# OutputConnectors.net
KiCad netlist of a schematic drawn in Altium Designer
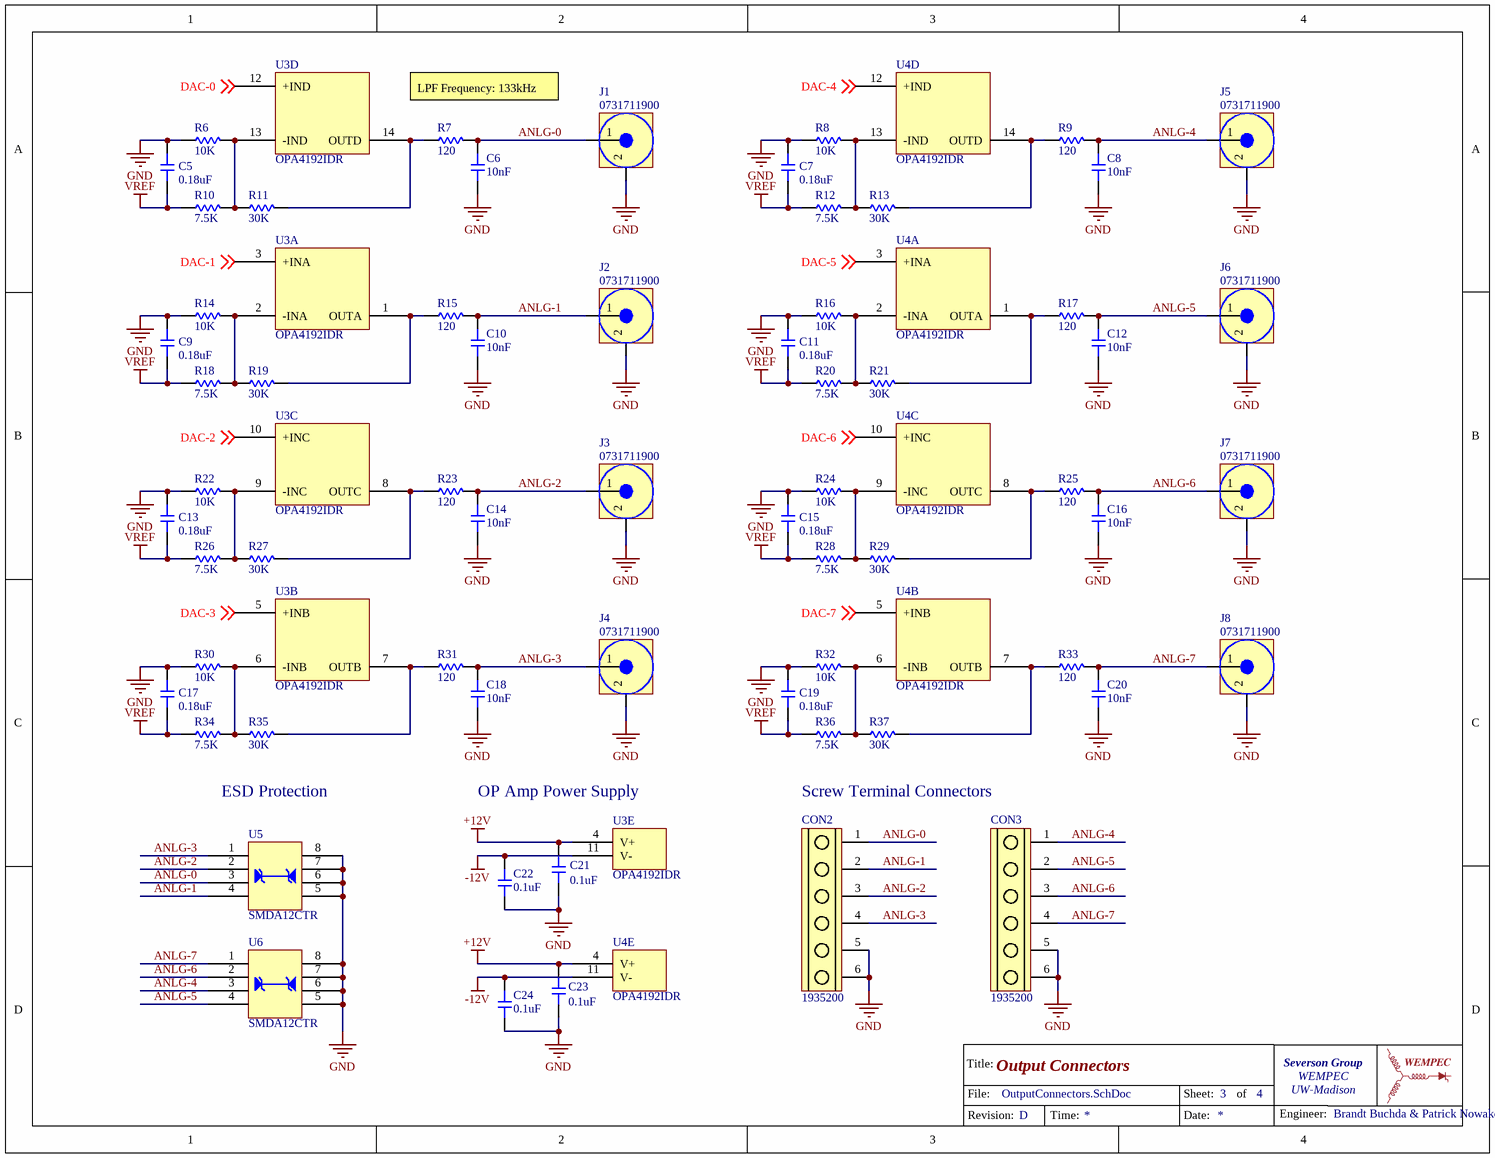
[diagram p0: OutputConnectors.SchDoc]

(export (version "E")
  (design (tool "Eeschema 10.0.6"))
  (components
    (comp (ref "C5")
      (value "0.18uF")
      (footprint "0603-CAP")
      (description "0.18µF ±10% 16V Ceramic Capacitor X7R 0603 (1608 Metric)")
      (fields (field (name "Comment") "CC0603KRX7R7BB184"))
      (libsource (lib "DAC") (part "Capacitor 0.18uF"))
    )
    (comp (ref "C6")
      (value "10nF")
      (footprint "0603-CAP")
      (description "10000pF ±10% 50V Ceramic Capacitor X7R 0603 (1608 Metric)")
      (fields (field (name "Comment") "CC0603KRX7R9BB103"))
      (libsource (lib "DAC") (part "Capacitor 10nF"))
    )
    (comp (ref "C7")
      (value "0.18uF")
      (footprint "0603-CAP")
      (description "0.18µF ±10% 16V Ceramic Capacitor X7R 0603 (1608 Metric)")
      (fields (field (name "Comment") "CC0603KRX7R7BB184"))
      (libsource (lib "DAC") (part "Capacitor 0.18uF"))
    )
    (comp (ref "C8")
      (value "10nF")
      (footprint "0603-CAP")
      (description "10000pF ±10% 50V Ceramic Capacitor X7R 0603 (1608 Metric)")
      (fields (field (name "Comment") "CC0603KRX7R9BB103"))
      (libsource (lib "DAC") (part "Capacitor 10nF"))
    )
    (comp (ref "C9")
      (value "0.18uF")
      (footprint "0603-CAP")
      (description "0.18µF ±10% 16V Ceramic Capacitor X7R 0603 (1608 Metric)")
      (fields (field (name "Comment") "CC0603KRX7R7BB184"))
      (libsource (lib "DAC") (part "Capacitor 0.18uF"))
    )
    (comp (ref "C10")
      (value "10nF")
      (footprint "0603-CAP")
      (description "10000pF ±10% 50V Ceramic Capacitor X7R 0603 (1608 Metric)")
      (fields (field (name "Comment") "CC0603KRX7R9BB103"))
      (libsource (lib "DAC") (part "Capacitor 10nF"))
    )
    (comp (ref "C11")
      (value "0.18uF")
      (footprint "0603-CAP")
      (description "0.18µF ±10% 16V Ceramic Capacitor X7R 0603 (1608 Metric)")
      (fields (field (name "Comment") "CC0603KRX7R7BB184"))
      (libsource (lib "DAC") (part "Capacitor 0.18uF"))
    )
    (comp (ref "C12")
      (value "10nF")
      (footprint "0603-CAP")
      (description "10000pF ±10% 50V Ceramic Capacitor X7R 0603 (1608 Metric)")
      (fields (field (name "Comment") "CC0603KRX7R9BB103"))
      (libsource (lib "DAC") (part "Capacitor 10nF"))
    )
    (comp (ref "C13")
      (value "0.18uF")
      (footprint "0603-CAP")
      (description "0.18µF ±10% 16V Ceramic Capacitor X7R 0603 (1608 Metric)")
      (fields (field (name "Comment") "CC0603KRX7R7BB184"))
      (libsource (lib "DAC") (part "Capacitor 0.18uF"))
    )
    (comp (ref "C14")
      (value "10nF")
      (footprint "0603-CAP")
      (description "10000pF ±10% 50V Ceramic Capacitor X7R 0603 (1608 Metric)")
      (fields (field (name "Comment") "CC0603KRX7R9BB103"))
      (libsource (lib "DAC") (part "Capacitor 10nF"))
    )
    (comp (ref "C15")
      (value "0.18uF")
      (footprint "0603-CAP")
      (description "0.18µF ±10% 16V Ceramic Capacitor X7R 0603 (1608 Metric)")
      (fields (field (name "Comment") "CC0603KRX7R7BB184"))
      (libsource (lib "DAC") (part "Capacitor 0.18uF"))
    )
    (comp (ref "C16")
      (value "10nF")
      (footprint "0603-CAP")
      (description "10000pF ±10% 50V Ceramic Capacitor X7R 0603 (1608 Metric)")
      (fields (field (name "Comment") "CC0603KRX7R9BB103"))
      (libsource (lib "DAC") (part "Capacitor 10nF"))
    )
    (comp (ref "C17")
      (value "0.18uF")
      (footprint "0603-CAP")
      (description "0.18µF ±10% 16V Ceramic Capacitor X7R 0603 (1608 Metric)")
      (fields (field (name "Comment") "CC0603KRX7R7BB184"))
      (libsource (lib "DAC") (part "Capacitor 0.18uF"))
    )
    (comp (ref "C18")
      (value "10nF")
      (footprint "0603-CAP")
      (description "10000pF ±10% 50V Ceramic Capacitor X7R 0603 (1608 Metric)")
      (fields (field (name "Comment") "CC0603KRX7R9BB103"))
      (libsource (lib "DAC") (part "Capacitor 10nF"))
    )
    (comp (ref "C19")
      (value "0.18uF")
      (footprint "0603-CAP")
      (description "0.18µF ±10% 16V Ceramic Capacitor X7R 0603 (1608 Metric)")
      (fields (field (name "Comment") "CC0603KRX7R7BB184"))
      (libsource (lib "DAC") (part "Capacitor 0.18uF"))
    )
    (comp (ref "C20")
      (value "10nF")
      (footprint "0603-CAP")
      (description "10000pF ±10% 50V Ceramic Capacitor X7R 0603 (1608 Metric)")
      (fields (field (name "Comment") "CC0603KRX7R9BB103"))
      (libsource (lib "DAC") (part "Capacitor 10nF"))
    )
    (comp (ref "C21")
      (value "0.1uF")
      (footprint "0603-CAP")
      (description "0.1µF ±10% 25V Ceramic Capacitor X7R 0603 (1608 Metric)")
      (fields (field (name "Comment") "CC0603KRX7R8BB104"))
      (libsource (lib "DAC") (part "Capacitor 0.1uF"))
    )
    (comp (ref "C22")
      (value "0.1uF")
      (footprint "0603-CAP")
      (description "0.1µF ±10% 25V Ceramic Capacitor X7R 0603 (1608 Metric)")
      (fields (field (name "Comment") "CC0603KRX7R8BB104"))
      (libsource (lib "DAC") (part "Capacitor 0.1uF"))
    )
    (comp (ref "C23")
      (value "0.1uF")
      (footprint "0603-CAP")
      (description "0.1µF ±10% 25V Ceramic Capacitor X7R 0603 (1608 Metric)")
      (fields (field (name "Comment") "CC0603KRX7R8BB104"))
      (libsource (lib "DAC") (part "Capacitor 0.1uF"))
    )
    (comp (ref "C24")
      (value "0.1uF")
      (footprint "0603-CAP")
      (description "0.1µF ±10% 25V Ceramic Capacitor X7R 0603 (1608 Metric)")
      (fields (field (name "Comment") "CC0603KRX7R8BB104"))
      (libsource (lib "DAC") (part "Capacitor 0.1uF"))
    )
    (comp (ref "CON2")
      (value "1935200")
      (footprint "1935200")
      (description "6 Position Wire to Board Terminal Block Horizontal with Board 0.197\" (5.00mm) Through Hole")
      (libsource (lib "DAC") (part "1935200"))
    )
    (comp (ref "CON3")
      (value "1935200")
      (footprint "1935200")
      (description "6 Position Wire to Board Terminal Block Horizontal with Board 0.197\" (5.00mm) Through Hole")
      (libsource (lib "DAC") (part "1935200"))
    )
    (comp (ref "J1")
      (value "0731711900")
      (footprint "0731711900")
      (description "CONN BNC JACK STR 75 OHM PCB")
      (libsource (lib "DAC") (part "0731711900"))
    )
    (comp (ref "J2")
      (value "0731711900")
      (footprint "0731711900")
      (description "CONN BNC JACK STR 75 OHM PCB")
      (libsource (lib "DAC") (part "0731711900"))
    )
    (comp (ref "J3")
      (value "0731711900")
      (footprint "0731711900")
      (description "CONN BNC JACK STR 75 OHM PCB")
      (libsource (lib "DAC") (part "0731711900"))
    )
    (comp (ref "J4")
      (value "0731711900")
      (footprint "0731711900")
      (description "CONN BNC JACK STR 75 OHM PCB")
      (libsource (lib "DAC") (part "0731711900"))
    )
    (comp (ref "J5")
      (value "0731711900")
      (footprint "0731711900")
      (description "CONN BNC JACK STR 75 OHM PCB")
      (libsource (lib "DAC") (part "0731711900"))
    )
    (comp (ref "J6")
      (value "0731711900")
      (footprint "0731711900")
      (description "CONN BNC JACK STR 75 OHM PCB")
      (libsource (lib "DAC") (part "0731711900"))
    )
    (comp (ref "J7")
      (value "0731711900")
      (footprint "0731711900")
      (description "CONN BNC JACK STR 75 OHM PCB")
      (libsource (lib "DAC") (part "0731711900"))
    )
    (comp (ref "J8")
      (value "0731711900")
      (footprint "0731711900")
      (description "CONN BNC JACK STR 75 OHM PCB")
      (libsource (lib "DAC") (part "0731711900"))
    )
    (comp (ref "R6")
      (value "10K")
      (footprint "0603-RES")
      (fields (field (name "Comment") "ERJ-PB3B1002V"))
      (libsource (lib "DAC") (part "Resistor 10K"))
    )
    (comp (ref "R7")
      (value "120")
      (footprint "0603-RES")
      (description "120 Ohms ±1% 0.1W, 1/10W Chip Resistor 0603 (1608 Metric) Moisture Resistant Thick Film")
      (fields (field (name "Comment") "RC0603FR-07120RL"))
      (libsource (lib "DAC") (part "Resistor 120"))
    )
    (comp (ref "R8")
      (value "10K")
      (footprint "0603-RES")
      (fields (field (name "Comment") "ERJ-PB3B1002V"))
      (libsource (lib "DAC") (part "Resistor 10K"))
    )
    (comp (ref "R9")
      (value "120")
      (footprint "0603-RES")
      (description "120 Ohms ±1% 0.1W, 1/10W Chip Resistor 0603 (1608 Metric) Moisture Resistant Thick Film")
      (fields (field (name "Comment") "RC0603FR-07120RL"))
      (libsource (lib "DAC") (part "Resistor 120"))
    )
    (comp (ref "R10")
      (value "7.5K")
      (footprint "0603-RES")
      (fields (field (name "Comment") "ERJ-PB3B7501V"))
      (libsource (lib "DAC") (part "Resistor 7.5K"))
    )
    (comp (ref "R11")
      (value "30K")
      (footprint "0603-RES")
      (fields (field (name "Comment") "ERJ-PB3B3002V"))
      (libsource (lib "DAC") (part "Resistor 30K"))
    )
    (comp (ref "R12")
      (value "7.5K")
      (footprint "0603-RES")
      (fields (field (name "Comment") "ERJ-PB3B7501V"))
      (libsource (lib "DAC") (part "Resistor 7.5K"))
    )
    (comp (ref "R13")
      (value "30K")
      (footprint "0603-RES")
      (fields (field (name "Comment") "ERJ-PB3B3002V"))
      (libsource (lib "DAC") (part "Resistor 30K"))
    )
    (comp (ref "R14")
      (value "10K")
      (footprint "0603-RES")
      (fields (field (name "Comment") "ERJ-PB3B1002V"))
      (libsource (lib "DAC") (part "Resistor 10K"))
    )
    (comp (ref "R15")
      (value "120")
      (footprint "0603-RES")
      (description "120 Ohms ±1% 0.1W, 1/10W Chip Resistor 0603 (1608 Metric) Moisture Resistant Thick Film")
      (fields (field (name "Comment") "RC0603FR-07120RL"))
      (libsource (lib "DAC") (part "Resistor 120"))
    )
    (comp (ref "R16")
      (value "10K")
      (footprint "0603-RES")
      (fields (field (name "Comment") "ERJ-PB3B1002V"))
      (libsource (lib "DAC") (part "Resistor 10K"))
    )
    (comp (ref "R17")
      (value "120")
      (footprint "0603-RES")
      (description "120 Ohms ±1% 0.1W, 1/10W Chip Resistor 0603 (1608 Metric) Moisture Resistant Thick Film")
      (fields (field (name "Comment") "RC0603FR-07120RL"))
      (libsource (lib "DAC") (part "Resistor 120"))
    )
    (comp (ref "R18")
      (value "7.5K")
      (footprint "0603-RES")
      (fields (field (name "Comment") "ERJ-PB3B7501V"))
      (libsource (lib "DAC") (part "Resistor 7.5K"))
    )
    (comp (ref "R19")
      (value "30K")
      (footprint "0603-RES")
      (fields (field (name "Comment") "ERJ-PB3B3002V"))
      (libsource (lib "DAC") (part "Resistor 30K"))
    )
    (comp (ref "R20")
      (value "7.5K")
      (footprint "0603-RES")
      (fields (field (name "Comment") "ERJ-PB3B7501V"))
      (libsource (lib "DAC") (part "Resistor 7.5K"))
    )
    (comp (ref "R21")
      (value "30K")
      (footprint "0603-RES")
      (fields (field (name "Comment") "ERJ-PB3B3002V"))
      (libsource (lib "DAC") (part "Resistor 30K"))
    )
    (comp (ref "R22")
      (value "10K")
      (footprint "0603-RES")
      (fields (field (name "Comment") "ERJ-PB3B1002V"))
      (libsource (lib "DAC") (part "Resistor 10K"))
    )
    (comp (ref "R23")
      (value "120")
      (footprint "0603-RES")
      (description "120 Ohms ±1% 0.1W, 1/10W Chip Resistor 0603 (1608 Metric) Moisture Resistant Thick Film")
      (fields (field (name "Comment") "RC0603FR-07120RL"))
      (libsource (lib "DAC") (part "Resistor 120"))
    )
    (comp (ref "R24")
      (value "10K")
      (footprint "0603-RES")
      (fields (field (name "Comment") "ERJ-PB3B1002V"))
      (libsource (lib "DAC") (part "Resistor 10K"))
    )
    (comp (ref "R25")
      (value "120")
      (footprint "0603-RES")
      (description "120 Ohms ±1% 0.1W, 1/10W Chip Resistor 0603 (1608 Metric) Moisture Resistant Thick Film")
      (fields (field (name "Comment") "RC0603FR-07120RL"))
      (libsource (lib "DAC") (part "Resistor 120"))
    )
    (comp (ref "R26")
      (value "7.5K")
      (footprint "0603-RES")
      (fields (field (name "Comment") "ERJ-PB3B7501V"))
      (libsource (lib "DAC") (part "Resistor 7.5K"))
    )
    (comp (ref "R27")
      (value "30K")
      (footprint "0603-RES")
      (fields (field (name "Comment") "ERJ-PB3B3002V"))
      (libsource (lib "DAC") (part "Resistor 30K"))
    )
    (comp (ref "R28")
      (value "7.5K")
      (footprint "0603-RES")
      (fields (field (name "Comment") "ERJ-PB3B7501V"))
      (libsource (lib "DAC") (part "Resistor 7.5K"))
    )
    (comp (ref "R29")
      (value "30K")
      (footprint "0603-RES")
      (fields (field (name "Comment") "ERJ-PB3B3002V"))
      (libsource (lib "DAC") (part "Resistor 30K"))
    )
    (comp (ref "R30")
      (value "10K")
      (footprint "0603-RES")
      (fields (field (name "Comment") "ERJ-PB3B1002V"))
      (libsource (lib "DAC") (part "Resistor 10K"))
    )
    (comp (ref "R31")
      (value "120")
      (footprint "0603-RES")
      (description "120 Ohms ±1% 0.1W, 1/10W Chip Resistor 0603 (1608 Metric) Moisture Resistant Thick Film")
      (fields (field (name "Comment") "RC0603FR-07120RL"))
      (libsource (lib "DAC") (part "Resistor 120"))
    )
    (comp (ref "R32")
      (value "10K")
      (footprint "0603-RES")
      (fields (field (name "Comment") "ERJ-PB3B1002V"))
      (libsource (lib "DAC") (part "Resistor 10K"))
    )
    (comp (ref "R33")
      (value "120")
      (footprint "0603-RES")
      (description "120 Ohms ±1% 0.1W, 1/10W Chip Resistor 0603 (1608 Metric) Moisture Resistant Thick Film")
      (fields (field (name "Comment") "RC0603FR-07120RL"))
      (libsource (lib "DAC") (part "Resistor 120"))
    )
    (comp (ref "R34")
      (value "7.5K")
      (footprint "0603-RES")
      (fields (field (name "Comment") "ERJ-PB3B7501V"))
      (libsource (lib "DAC") (part "Resistor 7.5K"))
    )
    (comp (ref "R35")
      (value "30K")
      (footprint "0603-RES")
      (fields (field (name "Comment") "ERJ-PB3B3002V"))
      (libsource (lib "DAC") (part "Resistor 30K"))
    )
    (comp (ref "R36")
      (value "7.5K")
      (footprint "0603-RES")
      (fields (field (name "Comment") "ERJ-PB3B7501V"))
      (libsource (lib "DAC") (part "Resistor 7.5K"))
    )
    (comp (ref "R37")
      (value "30K")
      (footprint "0603-RES")
      (fields (field (name "Comment") "ERJ-PB3B3002V"))
      (libsource (lib "DAC") (part "Resistor 30K"))
    )
    (comp (ref "U3")
      (value "OPA4192IDR")
      (footprint "SOIC127P600X175-14N")
      (description "General Purpose Amplifier 4 Circuit Rail-to-Rail 14-SOIC")
      (libsource (lib "DAC") (part "OPA4192IDR"))
    )
    (comp (ref "U4")
      (value "OPA4192IDR")
      (footprint "SOIC127P600X175-14N")
      (description "General Purpose Amplifier 4 Circuit Rail-to-Rail 14-SOIC")
      (libsource (lib "DAC") (part "OPA4192IDR"))
    )
    (comp (ref "U5")
      (value "SMDA12CTR")
      (footprint "SOIC127P600X175-8N-B")
      (description "19V Clamp 1A (8/20µs) Ipp TVS Diode Surface Mount 8-SO. No common node.")
      (libsource (lib "DAC") (part "SMDA12CTR"))
    )
    (comp (ref "U6")
      (value "SMDA12CTR")
      (footprint "SOIC127P600X175-8N-B")
      (description "19V Clamp 1A (8/20µs) Ipp TVS Diode Surface Mount 8-SO. No common node.")
      (libsource (lib "DAC") (part "SMDA12CTR"))
    )
  )
  (nets
    (net (code "1") (name "+12V") (class "Default")
      (node (ref "C21") (pin "2") (pinfunction "2_2") (pintype "passive"))
      (node (ref "C23") (pin "2") (pinfunction "2_2") (pintype "passive"))
      (node (ref "U3") (pin "4") (pinfunction "V+_4") (pintype "passive"))
      (node (ref "U4") (pin "4") (pinfunction "V+_4") (pintype "passive"))
    )
    (net (code "2") (name "-12V") (class "Default")
      (node (ref "C22") (pin "2") (pinfunction "2_2") (pintype "passive"))
      (node (ref "C24") (pin "2") (pinfunction "2_2") (pintype "passive"))
      (node (ref "U3") (pin "11") (pinfunction "V-_11") (pintype "passive"))
      (node (ref "U4") (pin "11") (pinfunction "V-_11") (pintype "passive"))
    )
    (net (code "3") (name "/ANLG-0") (class "Default")
      (node (ref "C6") (pin "2") (pinfunction "2_2") (pintype "passive"))
      (node (ref "CON2") (pin "1") (pinfunction "12_1") (pintype "passive"))
      (node (ref "J1") (pin "1") (pinfunction "ANLG_1") (pintype "passive"))
      (node (ref "R7") (pin "2") (pinfunction "2_2") (pintype "passive"))
      (node (ref "U5") (pin "3") (pinfunction "3_3") (pintype "passive"))
    )
    (net (code "4") (name "/ANLG-1") (class "Default")
      (node (ref "C10") (pin "2") (pinfunction "2_2") (pintype "passive"))
      (node (ref "CON2") (pin "2") (pinfunction "13_2") (pintype "passive"))
      (node (ref "J2") (pin "1") (pinfunction "ANLG_1") (pintype "passive"))
      (node (ref "R15") (pin "2") (pinfunction "2_2") (pintype "passive"))
      (node (ref "U5") (pin "4") (pinfunction "4_4") (pintype "passive"))
    )
    (net (code "5") (name "/ANLG-2") (class "Default")
      (node (ref "C14") (pin "2") (pinfunction "2_2") (pintype "passive"))
      (node (ref "CON2") (pin "3") (pinfunction "3_3") (pintype "passive"))
      (node (ref "J3") (pin "1") (pinfunction "ANLG_1") (pintype "passive"))
      (node (ref "R23") (pin "2") (pinfunction "2_2") (pintype "passive"))
      (node (ref "U5") (pin "2") (pinfunction "2_2") (pintype "passive"))
    )
    (net (code "6") (name "/ANLG-3") (class "Default")
      (node (ref "C18") (pin "2") (pinfunction "2_2") (pintype "passive"))
      (node (ref "CON2") (pin "4") (pinfunction "4_4") (pintype "passive"))
      (node (ref "J4") (pin "1") (pinfunction "ANLG_1") (pintype "passive"))
      (node (ref "R31") (pin "2") (pinfunction "2_2") (pintype "passive"))
      (node (ref "U5") (pin "1") (pinfunction "1_1") (pintype "passive"))
    )
    (net (code "7") (name "/ANLG-4") (class "Default")
      (node (ref "C8") (pin "2") (pinfunction "2_2") (pintype "passive"))
      (node (ref "CON3") (pin "1") (pinfunction "12_1") (pintype "passive"))
      (node (ref "J5") (pin "1") (pinfunction "ANLG_1") (pintype "passive"))
      (node (ref "R9") (pin "2") (pinfunction "2_2") (pintype "passive"))
      (node (ref "U6") (pin "3") (pinfunction "3_3") (pintype "passive"))
    )
    (net (code "8") (name "/ANLG-5") (class "Default")
      (node (ref "C12") (pin "2") (pinfunction "2_2") (pintype "passive"))
      (node (ref "CON3") (pin "2") (pinfunction "13_2") (pintype "passive"))
      (node (ref "J6") (pin "1") (pinfunction "ANLG_1") (pintype "passive"))
      (node (ref "R17") (pin "2") (pinfunction "2_2") (pintype "passive"))
      (node (ref "U6") (pin "4") (pinfunction "4_4") (pintype "passive"))
    )
    (net (code "9") (name "/ANLG-6") (class "Default")
      (node (ref "C16") (pin "2") (pinfunction "2_2") (pintype "passive"))
      (node (ref "CON3") (pin "3") (pinfunction "3_3") (pintype "passive"))
      (node (ref "J7") (pin "1") (pinfunction "ANLG_1") (pintype "passive"))
      (node (ref "R25") (pin "2") (pinfunction "2_2") (pintype "passive"))
      (node (ref "U6") (pin "2") (pinfunction "2_2") (pintype "passive"))
    )
    (net (code "10") (name "/ANLG-7") (class "Default")
      (node (ref "C20") (pin "2") (pinfunction "2_2") (pintype "passive"))
      (node (ref "CON3") (pin "4") (pinfunction "4_4") (pintype "passive"))
      (node (ref "J8") (pin "1") (pinfunction "ANLG_1") (pintype "passive"))
      (node (ref "R33") (pin "2") (pinfunction "2_2") (pintype "passive"))
      (node (ref "U6") (pin "1") (pinfunction "1_1") (pintype "passive"))
    )
    (net (code "11") (name "DAC-0") (class "Default")
      (node (ref "U3") (pin "12") (pinfunction "+IND_12") (pintype "passive"))
    )
    (net (code "12") (name "DAC-1") (class "Default")
      (node (ref "U3") (pin "3") (pinfunction "+INA_3") (pintype "passive"))
    )
    (net (code "13") (name "DAC-2") (class "Default")
      (node (ref "U3") (pin "10") (pinfunction "+INC_10") (pintype "passive"))
    )
    (net (code "14") (name "DAC-3") (class "Default")
      (node (ref "U3") (pin "5") (pinfunction "+INB_5") (pintype "passive"))
    )
    (net (code "15") (name "DAC-4") (class "Default")
      (node (ref "U4") (pin "12") (pinfunction "+IND_12") (pintype "passive"))
    )
    (net (code "16") (name "DAC-5") (class "Default")
      (node (ref "U4") (pin "3") (pinfunction "+INA_3") (pintype "passive"))
    )
    (net (code "17") (name "DAC-6") (class "Default")
      (node (ref "U4") (pin "10") (pinfunction "+INC_10") (pintype "passive"))
    )
    (net (code "18") (name "DAC-7") (class "Default")
      (node (ref "U4") (pin "5") (pinfunction "+INB_5") (pintype "passive"))
    )
    (net (code "19") (name "GND") (class "Default")
      (node (ref "C10") (pin "1") (pinfunction "1_1") (pintype "passive"))
      (node (ref "C11") (pin "2") (pinfunction "2_2") (pintype "passive"))
      (node (ref "C12") (pin "1") (pinfunction "1_1") (pintype "passive"))
      (node (ref "C13") (pin "2") (pinfunction "2_2") (pintype "passive"))
      (node (ref "C14") (pin "1") (pinfunction "1_1") (pintype "passive"))
      (node (ref "C15") (pin "2") (pinfunction "2_2") (pintype "passive"))
      (node (ref "C16") (pin "1") (pinfunction "1_1") (pintype "passive"))
      (node (ref "C17") (pin "2") (pinfunction "2_2") (pintype "passive"))
      (node (ref "C18") (pin "1") (pinfunction "1_1") (pintype "passive"))
      (node (ref "C19") (pin "2") (pinfunction "2_2") (pintype "passive"))
      (node (ref "C20") (pin "1") (pinfunction "1_1") (pintype "passive"))
      (node (ref "C21") (pin "1") (pinfunction "1_1") (pintype "passive"))
      (node (ref "C22") (pin "1") (pinfunction "1_1") (pintype "passive"))
      (node (ref "C23") (pin "1") (pinfunction "1_1") (pintype "passive"))
      (node (ref "C24") (pin "1") (pinfunction "1_1") (pintype "passive"))
      (node (ref "C5") (pin "2") (pinfunction "2_2") (pintype "passive"))
      (node (ref "C6") (pin "1") (pinfunction "1_1") (pintype "passive"))
      (node (ref "C7") (pin "2") (pinfunction "2_2") (pintype "passive"))
      (node (ref "C8") (pin "1") (pinfunction "1_1") (pintype "passive"))
      (node (ref "C9") (pin "2") (pinfunction "2_2") (pintype "passive"))
      (node (ref "CON2") (pin "5") (pinfunction "5_5") (pintype "passive"))
      (node (ref "CON2") (pin "6") (pinfunction "6_6") (pintype "passive"))
      (node (ref "CON3") (pin "5") (pinfunction "5_5") (pintype "passive"))
      (node (ref "CON3") (pin "6") (pinfunction "6_6") (pintype "passive"))
      (node (ref "J1") (pin "2") (pinfunction "GND_2") (pintype "passive"))
      (node (ref "J2") (pin "2") (pinfunction "GND_2") (pintype "passive"))
      (node (ref "J3") (pin "2") (pinfunction "GND_2") (pintype "passive"))
      (node (ref "J4") (pin "2") (pinfunction "GND_2") (pintype "passive"))
      (node (ref "J5") (pin "2") (pinfunction "GND_2") (pintype "passive"))
      (node (ref "J6") (pin "2") (pinfunction "GND_2") (pintype "passive"))
      (node (ref "J7") (pin "2") (pinfunction "GND_2") (pintype "passive"))
      (node (ref "J8") (pin "2") (pinfunction "GND_2") (pintype "passive"))
      (node (ref "R14") (pin "1") (pinfunction "1_1") (pintype "passive"))
      (node (ref "R16") (pin "1") (pinfunction "1_1") (pintype "passive"))
      (node (ref "R22") (pin "1") (pinfunction "1_1") (pintype "passive"))
      (node (ref "R24") (pin "1") (pinfunction "1_1") (pintype "passive"))
      (node (ref "R30") (pin "1") (pinfunction "1_1") (pintype "passive"))
      (node (ref "R32") (pin "1") (pinfunction "1_1") (pintype "passive"))
      (node (ref "R6") (pin "1") (pinfunction "1_1") (pintype "passive"))
      (node (ref "R8") (pin "1") (pinfunction "1_1") (pintype "passive"))
      (node (ref "U5") (pin "5") (pinfunction "5_5") (pintype "passive"))
      (node (ref "U5") (pin "6") (pinfunction "6_6") (pintype "passive"))
      (node (ref "U5") (pin "7") (pinfunction "7_7") (pintype "passive"))
      (node (ref "U5") (pin "8") (pinfunction "8_8") (pintype "passive"))
      (node (ref "U6") (pin "5") (pinfunction "5_5") (pintype "passive"))
      (node (ref "U6") (pin "6") (pinfunction "6_6") (pintype "passive"))
      (node (ref "U6") (pin "7") (pinfunction "7_7") (pintype "passive"))
      (node (ref "U6") (pin "8") (pinfunction "8_8") (pintype "passive"))
    )
    (net (code "20") (name "Net-(U3A--INA)") (class "Default")
      (node (ref "R14") (pin "2") (pinfunction "2_2") (pintype "passive"))
      (node (ref "R18") (pin "2") (pinfunction "2_2") (pintype "passive"))
      (node (ref "R19") (pin "1") (pinfunction "1_1") (pintype "passive"))
      (node (ref "U3") (pin "2") (pinfunction "-INA_2") (pintype "passive"))
    )
    (net (code "21") (name "Net-(U3A-OUTA)") (class "Default")
      (node (ref "R15") (pin "1") (pinfunction "1_1") (pintype "passive"))
      (node (ref "R19") (pin "2") (pinfunction "2_2") (pintype "passive"))
      (node (ref "U3") (pin "1") (pinfunction "OUTA_1") (pintype "passive"))
    )
    (net (code "22") (name "Net-(U3B--INB)") (class "Default")
      (node (ref "R30") (pin "2") (pinfunction "2_2") (pintype "passive"))
      (node (ref "R34") (pin "2") (pinfunction "2_2") (pintype "passive"))
      (node (ref "R35") (pin "1") (pinfunction "1_1") (pintype "passive"))
      (node (ref "U3") (pin "6") (pinfunction "-INB_6") (pintype "passive"))
    )
    (net (code "23") (name "Net-(U3B-OUTB)") (class "Default")
      (node (ref "R31") (pin "1") (pinfunction "1_1") (pintype "passive"))
      (node (ref "R35") (pin "2") (pinfunction "2_2") (pintype "passive"))
      (node (ref "U3") (pin "7") (pinfunction "OUTB_7") (pintype "passive"))
    )
    (net (code "24") (name "Net-(U3C--INC)") (class "Default")
      (node (ref "R22") (pin "2") (pinfunction "2_2") (pintype "passive"))
      (node (ref "R26") (pin "2") (pinfunction "2_2") (pintype "passive"))
      (node (ref "R27") (pin "1") (pinfunction "1_1") (pintype "passive"))
      (node (ref "U3") (pin "9") (pinfunction "-INC_9") (pintype "passive"))
    )
    (net (code "25") (name "Net-(U3C-OUTC)") (class "Default")
      (node (ref "R23") (pin "1") (pinfunction "1_1") (pintype "passive"))
      (node (ref "R27") (pin "2") (pinfunction "2_2") (pintype "passive"))
      (node (ref "U3") (pin "8") (pinfunction "OUTC_8") (pintype "passive"))
    )
    (net (code "26") (name "Net-(U3D--IND)") (class "Default")
      (node (ref "R10") (pin "2") (pinfunction "2_2") (pintype "passive"))
      (node (ref "R11") (pin "1") (pinfunction "1_1") (pintype "passive"))
      (node (ref "R6") (pin "2") (pinfunction "2_2") (pintype "passive"))
      (node (ref "U3") (pin "13") (pinfunction "-IND_13") (pintype "passive"))
    )
    (net (code "27") (name "Net-(U3D-OUTD)") (class "Default")
      (node (ref "R11") (pin "2") (pinfunction "2_2") (pintype "passive"))
      (node (ref "R7") (pin "1") (pinfunction "1_1") (pintype "passive"))
      (node (ref "U3") (pin "14") (pinfunction "OUTD_14") (pintype "passive"))
    )
    (net (code "28") (name "Net-(U4A--INA)") (class "Default")
      (node (ref "R16") (pin "2") (pinfunction "2_2") (pintype "passive"))
      (node (ref "R20") (pin "2") (pinfunction "2_2") (pintype "passive"))
      (node (ref "R21") (pin "1") (pinfunction "1_1") (pintype "passive"))
      (node (ref "U4") (pin "2") (pinfunction "-INA_2") (pintype "passive"))
    )
    (net (code "29") (name "Net-(U4A-OUTA)") (class "Default")
      (node (ref "R17") (pin "1") (pinfunction "1_1") (pintype "passive"))
      (node (ref "R21") (pin "2") (pinfunction "2_2") (pintype "passive"))
      (node (ref "U4") (pin "1") (pinfunction "OUTA_1") (pintype "passive"))
    )
    (net (code "30") (name "Net-(U4B--INB)") (class "Default")
      (node (ref "R32") (pin "2") (pinfunction "2_2") (pintype "passive"))
      (node (ref "R36") (pin "2") (pinfunction "2_2") (pintype "passive"))
      (node (ref "R37") (pin "1") (pinfunction "1_1") (pintype "passive"))
      (node (ref "U4") (pin "6") (pinfunction "-INB_6") (pintype "passive"))
    )
    (net (code "31") (name "Net-(U4B-OUTB)") (class "Default")
      (node (ref "R33") (pin "1") (pinfunction "1_1") (pintype "passive"))
      (node (ref "R37") (pin "2") (pinfunction "2_2") (pintype "passive"))
      (node (ref "U4") (pin "7") (pinfunction "OUTB_7") (pintype "passive"))
    )
    (net (code "32") (name "Net-(U4C--INC)") (class "Default")
      (node (ref "R24") (pin "2") (pinfunction "2_2") (pintype "passive"))
      (node (ref "R28") (pin "2") (pinfunction "2_2") (pintype "passive"))
      (node (ref "R29") (pin "1") (pinfunction "1_1") (pintype "passive"))
      (node (ref "U4") (pin "9") (pinfunction "-INC_9") (pintype "passive"))
    )
    (net (code "33") (name "Net-(U4C-OUTC)") (class "Default")
      (node (ref "R25") (pin "1") (pinfunction "1_1") (pintype "passive"))
      (node (ref "R29") (pin "2") (pinfunction "2_2") (pintype "passive"))
      (node (ref "U4") (pin "8") (pinfunction "OUTC_8") (pintype "passive"))
    )
    (net (code "34") (name "Net-(U4D--IND)") (class "Default")
      (node (ref "R12") (pin "2") (pinfunction "2_2") (pintype "passive"))
      (node (ref "R13") (pin "1") (pinfunction "1_1") (pintype "passive"))
      (node (ref "R8") (pin "2") (pinfunction "2_2") (pintype "passive"))
      (node (ref "U4") (pin "13") (pinfunction "-IND_13") (pintype "passive"))
    )
    (net (code "35") (name "Net-(U4D-OUTD)") (class "Default")
      (node (ref "R13") (pin "2") (pinfunction "2_2") (pintype "passive"))
      (node (ref "R9") (pin "1") (pinfunction "1_1") (pintype "passive"))
      (node (ref "U4") (pin "14") (pinfunction "OUTD_14") (pintype "passive"))
    )
    (net (code "36") (name "VREF") (class "Default")
      (node (ref "C11") (pin "1") (pinfunction "1_1") (pintype "passive"))
      (node (ref "C13") (pin "1") (pinfunction "1_1") (pintype "passive"))
      (node (ref "C15") (pin "1") (pinfunction "1_1") (pintype "passive"))
      (node (ref "C17") (pin "1") (pinfunction "1_1") (pintype "passive"))
      (node (ref "C19") (pin "1") (pinfunction "1_1") (pintype "passive"))
      (node (ref "C5") (pin "1") (pinfunction "1_1") (pintype "passive"))
      (node (ref "C7") (pin "1") (pinfunction "1_1") (pintype "passive"))
      (node (ref "C9") (pin "1") (pinfunction "1_1") (pintype "passive"))
      (node (ref "R10") (pin "1") (pinfunction "1_1") (pintype "passive"))
      (node (ref "R12") (pin "1") (pinfunction "1_1") (pintype "passive"))
      (node (ref "R18") (pin "1") (pinfunction "1_1") (pintype "passive"))
      (node (ref "R20") (pin "1") (pinfunction "1_1") (pintype "passive"))
      (node (ref "R26") (pin "1") (pinfunction "1_1") (pintype "passive"))
      (node (ref "R28") (pin "1") (pinfunction "1_1") (pintype "passive"))
      (node (ref "R34") (pin "1") (pinfunction "1_1") (pintype "passive"))
      (node (ref "R36") (pin "1") (pinfunction "1_1") (pintype "passive"))
    )
  )
)
